# infra_stlink.net
KiCad netlist of a schematic drawn in Altium Designer
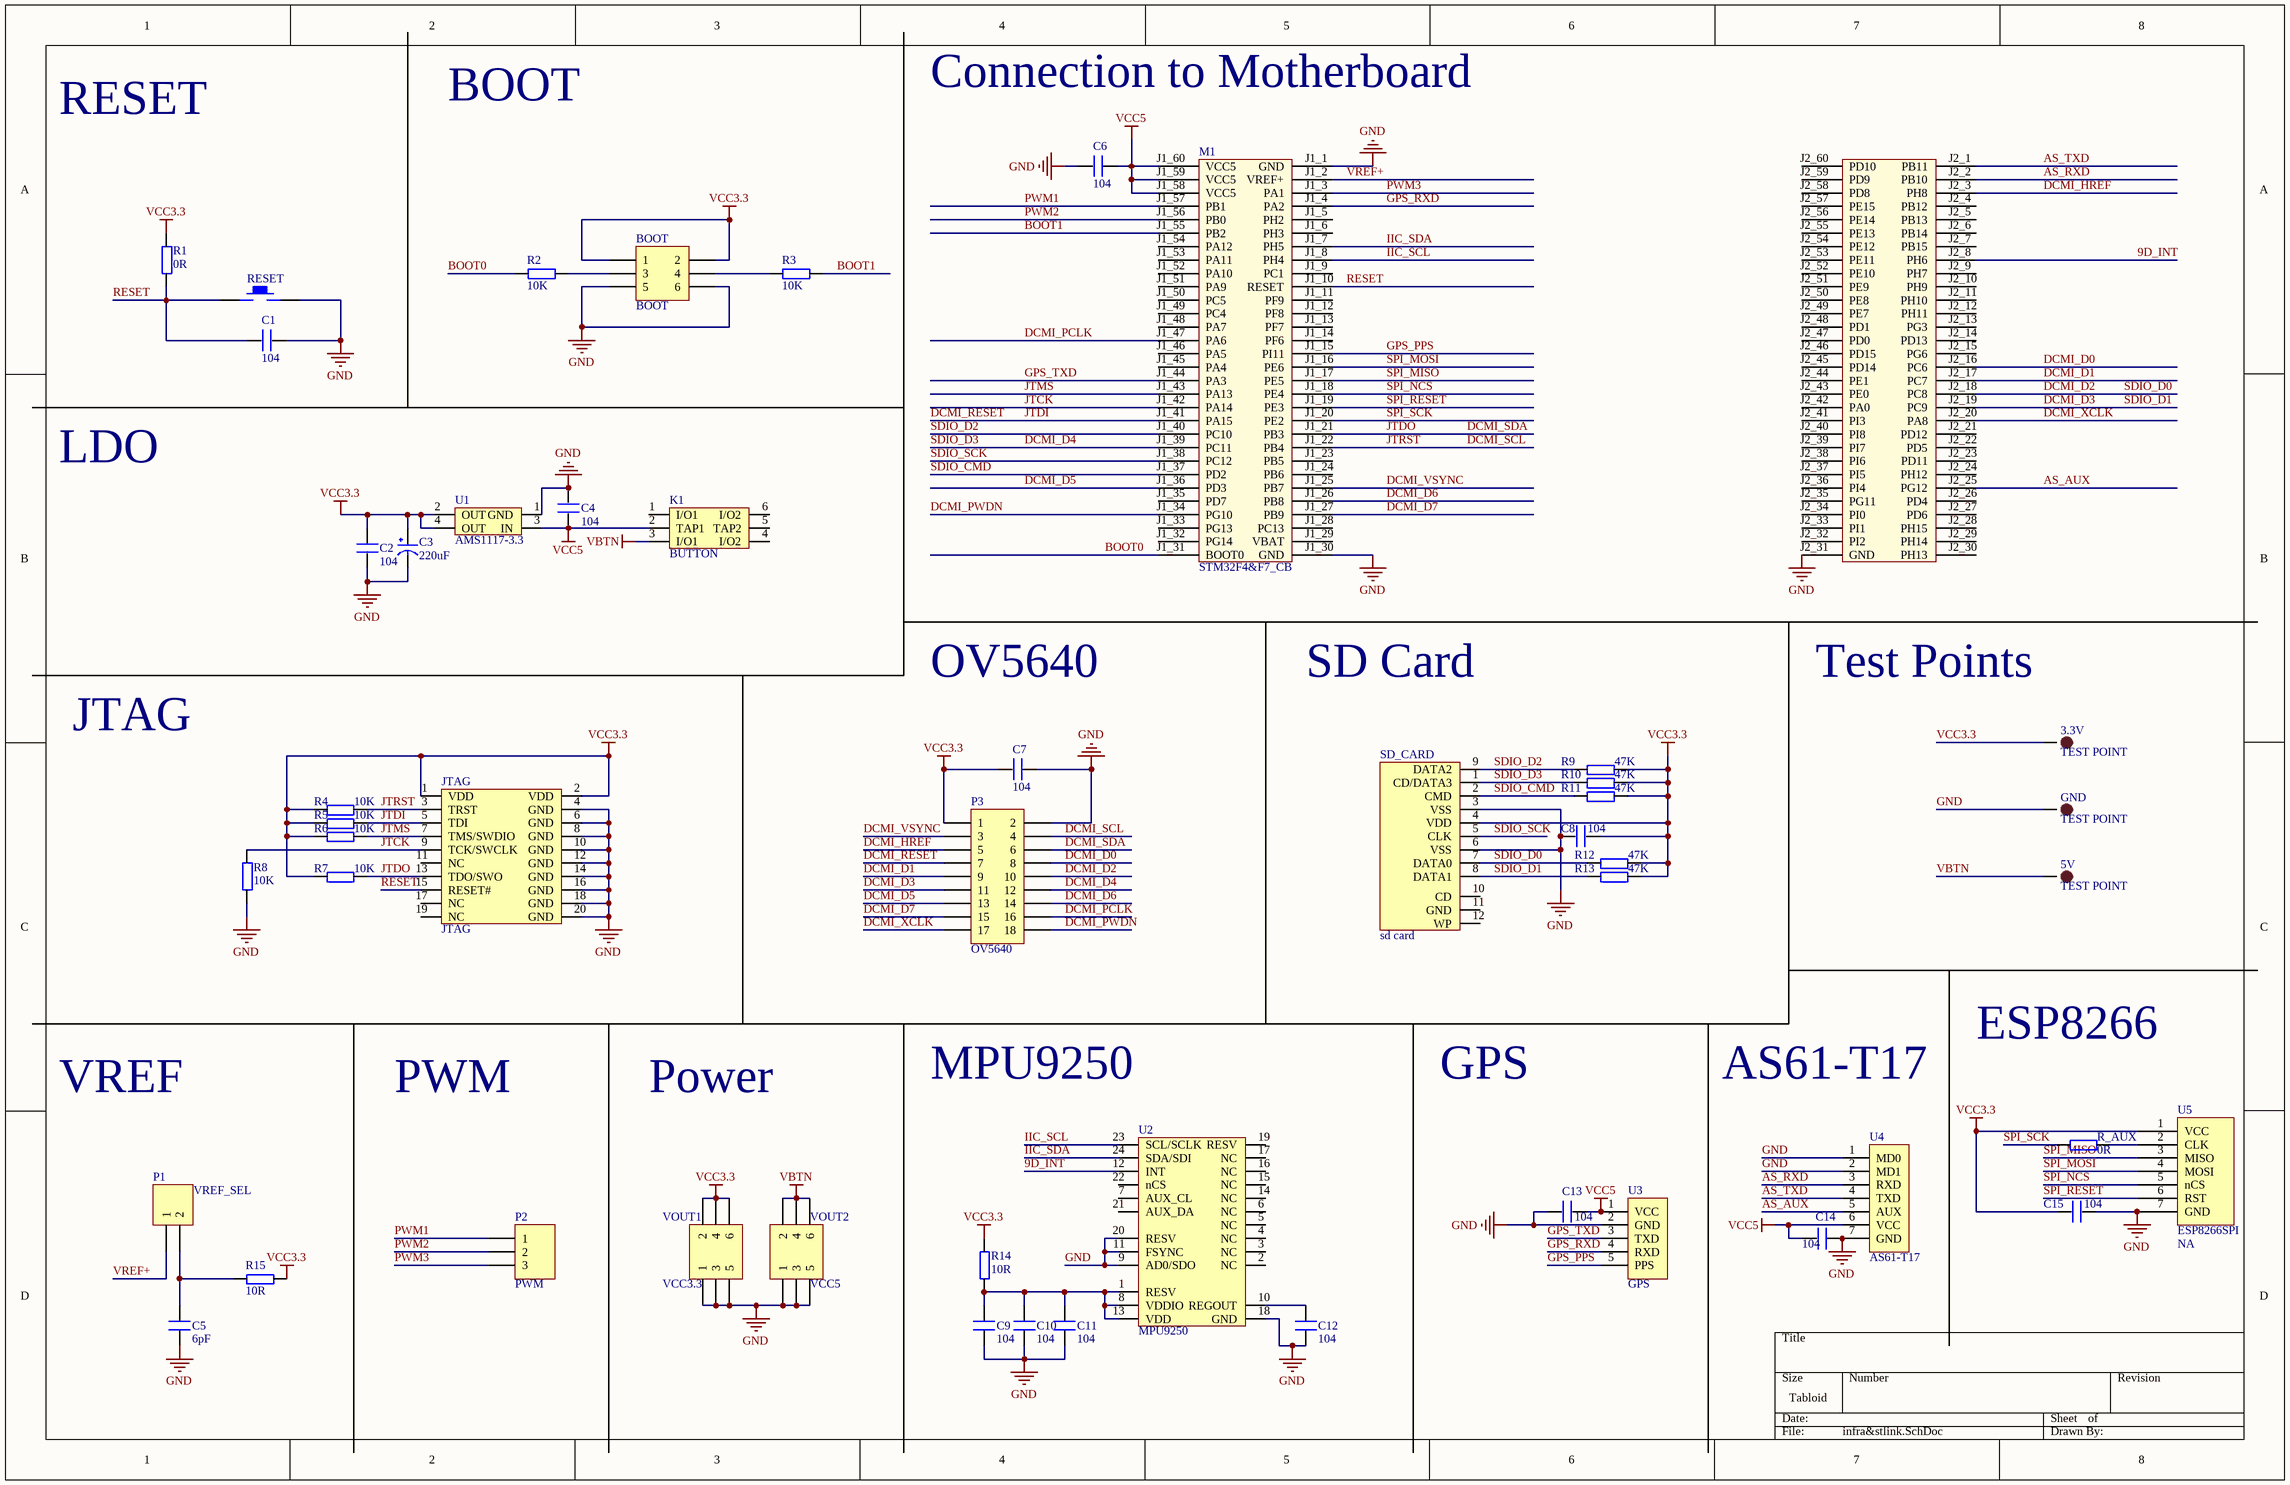
[diagram p0: infra&stlink.SchDoc]

(export (version "E")
  (design (tool "Eeschema 10.0.6"))
  (components
    (comp (ref "3.3V")
      (value "TEST POINT")
      (footprint "TP-1.5")
      (description "测试点")
      (libsource (lib "STM32F767核心板封装库") (part "TEST-POINT"))
    )
    (comp (ref "5V")
      (value "TEST POINT")
      (footprint "TP-1.5")
      (description "测试点")
      (libsource (lib "STM32F767核心板封装库") (part "TEST-POINT"))
    )
    (comp (ref "BOOT")
      (value "BOOT")
      (footprint "HDR2X3")
      (description "Header, 3-Pin, Dual row")
      (fields (field (name "PUBLISHER") "Altium Limited"))
      (libsource (lib "阿波罗STM32F4&F7底板封装库") (part "Header 3X2"))
    )
    (comp (ref "C1") (value "104") (footprint "0805") (libsource (lib "阿波罗STM32F4&F7底板封装库") (part "C")))
    (comp (ref "C2") (value "104") (footprint "0805") (libsource (lib "阿波罗STM32F4&F7底板封装库") (part "C")))
    (comp (ref "C3")
      (value "220uF")
      (footprint "CC6.56.5")
      (libsource (lib "阿波罗STM32F4&F7底板封装库") (part "CAP"))
    )
    (comp (ref "C4") (value "104") (footprint "0805") (libsource (lib "阿波罗STM32F4&F7底板封装库") (part "C")))
    (comp (ref "C5") (value "6pF") (footprint "0805") (libsource (lib "STM32F767核心板封装库") (part "C")))
    (comp (ref "C6") (value "104") (footprint "0805") (libsource (lib "阿波罗STM32F4&F7底板封装库") (part "C")))
    (comp (ref "C7") (value "104") (footprint "0805") (libsource (lib "STM32F767核心板封装库") (part "C")))
    (comp (ref "C8") (value "104") (footprint "0805") (libsource (lib "阿波罗STM32F4&F7底板封装库") (part "C")))
    (comp (ref "C9") (value "104") (footprint "0805") (libsource (lib "阿波罗STM32F4&F7底板封装库") (part "C")))
    (comp (ref "C10") (value "104") (footprint "0805") (libsource (lib "阿波罗STM32F4&F7底板封装库") (part "C")))
    (comp (ref "C11") (value "104") (footprint "0805") (libsource (lib "阿波罗STM32F4&F7底板封装库") (part "C")))
    (comp (ref "C12") (value "104") (footprint "0805") (libsource (lib "阿波罗STM32F4&F7底板封装库") (part "C")))
    (comp (ref "C13") (value "104") (footprint "0805") (libsource (lib "阿波罗STM32F4&F7底板封装库") (part "C")))
    (comp (ref "C14") (value "104") (footprint "0805") (libsource (lib "阿波罗STM32F4&F7底板封装库") (part "C")))
    (comp (ref "C15") (value "104") (footprint "0805") (libsource (lib "阿波罗STM32F4&F7底板封装库") (part "C")))
    (comp (ref "GND")
      (value "TEST POINT")
      (footprint "TP-1.5")
      (description "测试点")
      (libsource (lib "STM32F767核心板封装库") (part "TEST-POINT"))
    )
    (comp (ref "JTAG")
      (value "JTAG")
      (footprint "JTAG_20")
      (libsource (lib "阿波罗STM32F4&F7底板封装库") (part "JTAG"))
    )
    (comp (ref "K1")
      (value "BUTTON")
      (footprint "BTN8.5*8.5")
      (libsource (lib "阿波罗STM32F4&F7底板封装库") (part "BUTTON"))
    )
    (comp (ref "M1")
      (value "STM32F4&F7_CB")
      (footprint "STM32F4&F7_CB")
      (description "F429/746 Core Board")
      (libsource (lib "阿波罗STM32F4&F7底板封装库") (part "STM32F4&F7_CB"))
    )
    (comp (ref "P1")
      (value "VREF_SEL")
      (footprint "HDR1X2")
      (description "Header, 2-Pin")
      (fields (field (name "PUBLISHER") "Altium Limited"))
      (libsource (lib "阿波罗STM32F4&F7底板封装库") (part "Header 2"))
    )
    (comp (ref "P2")
      (value "PWM")
      (footprint "HDR1X3")
      (description "Header, 3-Pin")
      (fields (field (name "PUBLISHER") "Altium Limited"))
      (libsource (lib "Miscellaneous Connectors") (part "Header 3"))
    )
    (comp (ref "P3")
      (value "OV5640")
      (footprint "HDR2X9")
      (description "Header, 9-Pin, Dual row")
      (fields (field (name "PUBLISHER") "Altium Limited"))
      (libsource (lib "阿波罗STM32F4&F7底板封装库") (part "Header 9X2"))
    )
    (comp (ref "R1") (value "0R") (footprint "0805") (libsource (lib "STM32F767核心板封装库") (part "R")))
    (comp (ref "R2") (value "10K") (footprint "0805") (libsource (lib "STM32F767核心板封装库") (part "R")))
    (comp (ref "R3") (value "10K") (footprint "0805") (libsource (lib "STM32F767核心板封装库") (part "R")))
    (comp (ref "R4") (value "10K") (footprint "0805") (libsource (lib "STM32F767核心板封装库") (part "R")))
    (comp (ref "R5") (value "10K") (footprint "0805") (libsource (lib "STM32F767核心板封装库") (part "R")))
    (comp (ref "R6") (value "10K") (footprint "0805") (libsource (lib "STM32F767核心板封装库") (part "R")))
    (comp (ref "R7") (value "10K") (footprint "0805") (libsource (lib "STM32F767核心板封装库") (part "R")))
    (comp (ref "R8") (value "10K") (footprint "0805") (libsource (lib "STM32F767核心板封装库") (part "R")))
    (comp (ref "R9") (value "47K") (footprint "0805") (libsource (lib "STM32F767核心板封装库") (part "R")))
    (comp (ref "R10") (value "47K") (footprint "0805") (libsource (lib "STM32F767核心板封装库") (part "R")))
    (comp (ref "R11") (value "47K") (footprint "0805") (libsource (lib "STM32F767核心板封装库") (part "R")))
    (comp (ref "R12") (value "47K") (footprint "0805") (libsource (lib "STM32F767核心板封装库") (part "R")))
    (comp (ref "R13") (value "47K") (footprint "0805") (libsource (lib "STM32F767核心板封装库") (part "R")))
    (comp (ref "R14") (value "10R") (footprint "0805") (libsource (lib "STM32F767核心板封装库") (part "R")))
    (comp (ref "R15") (value "10R") (footprint "0805") (libsource (lib "STM32F767核心板封装库") (part "R")))
    (comp (ref "RESET")
      (value "KEY_M")
      (footprint "KEY_M")
      (libsource (lib "阿波罗STM32F4&F7底板封装库") (part "KEY_M"))
    )
    (comp (ref "R_AUX") (value "0R") (footprint "0805") (libsource (lib "STM32F767核心板封装库") (part "R")))
    (comp (ref "SD_CARD")
      (value "sd card")
      (footprint "SDCARD_L")
      (libsource (lib "阿波罗STM32F4&F7底板封装库") (part "sd card"))
    )
    (comp (ref "U1")
      (value "AMS1117-3.3")
      (footprint "AMS1117")
      (libsource (lib "阿波罗STM32F4&F7底板封装库") (part "AMS1117"))
    )
    (comp (ref "U2")
      (value "MPU9250")
      (footprint "QFN24-t")
      (description "9轴运动处理传感器")
      (libsource (lib "阿波罗STM32F4&F7底板封装库") (part "MPU9250"))
    )
    (comp (ref "U3")
      (value "GPS")
      (footprint "HDR1X5")
      (description "Header, 5-Pin")
      (fields (field (name "PUBLISHER") "Altium Limited"))
      (libsource (lib "Miscellaneous Connectors") (part "Header 5"))
    )
    (comp (ref "U4")
      (value "AS61-T17")
      (footprint "HDR1X7")
      (description "Header, 7-Pin")
      (fields (field (name "PUBLISHER") "Altium Limited"))
      (libsource (lib "Miscellaneous Connectors") (part "Header 7"))
    )
    (comp (ref "U5")
      (value "NA")
      (footprint "Edge Connector7")
      (libsource (lib "esp8266spi") (part "ESP8266SPI"))
    )
    (comp (ref "VOUT1")
      (value "VCC3.3")
      (footprint "HDR2X3")
      (description "Header, 3-Pin, Dual row")
      (fields (field (name "PUBLISHER") "Altium Limited"))
      (libsource (lib "Miscellaneous Connectors") (part "Header 3X2"))
    )
    (comp (ref "VOUT2")
      (value "VCC5")
      (footprint "HDR2X3")
      (description "Header, 3-Pin, Dual row")
      (fields (field (name "PUBLISHER") "Altium Limited"))
      (libsource (lib "Miscellaneous Connectors") (part "Header 3X2"))
    )
  )
  (nets
    (net (code "1") (name "/9D_INT") (class "Default")
      (node (ref "M1") (pin "J2_8") (pinfunction "PH6_J2_8") (pintype "passive"))
      (node (ref "U2") (pin "12") (pinfunction "INT_12") (pintype "passive"))
    )
    (net (code "2") (name "/AS_AUX") (class "Default")
      (node (ref "M1") (pin "J2_25") (pinfunction "PG12_J2_25") (pintype "passive"))
      (node (ref "U4") (pin "5") (pinfunction "AUX_5") (pintype "passive"))
    )
    (net (code "3") (name "/AS_RXD") (class "Default")
      (node (ref "M1") (pin "J2_2") (pinfunction "PB10_J2_2") (pintype "passive"))
      (node (ref "U4") (pin "3") (pinfunction "RXD_3") (pintype "passive"))
    )
    (net (code "4") (name "/AS_TXD") (class "Default")
      (node (ref "M1") (pin "J2_1") (pinfunction "PB11_J2_1") (pintype "passive"))
      (node (ref "U4") (pin "4") (pinfunction "TXD_4") (pintype "passive"))
    )
    (net (code "5") (name "/BOOT0") (class "Default")
      (node (ref "M1") (pin "J1_31") (pinfunction "BOOT0_J1_31") (pintype "passive"))
      (node (ref "R2") (pin "1") (pintype "passive"))
    )
    (net (code "6") (name "/BOOT1") (class "Default")
      (node (ref "M1") (pin "J1_55") (pinfunction "PB2_J1_55") (pintype "passive"))
      (node (ref "R3") (pin "2") (pintype "passive"))
    )
    (net (code "7") (name "/DCMI_D0") (class "Default")
      (node (ref "M1") (pin "J2_16") (pinfunction "PC6_J2_16") (pintype "passive"))
      (node (ref "P3") (pin "8") (pinfunction "8_8") (pintype "passive"))
    )
    (net (code "8") (name "/DCMI_D1") (class "Default")
      (node (ref "M1") (pin "J2_17") (pinfunction "PC7_J2_17") (pintype "passive"))
      (node (ref "P3") (pin "9") (pinfunction "9_9") (pintype "passive"))
    )
    (net (code "9") (name "/DCMI_D2") (class "Default")
      (node (ref "M1") (pin "J2_18") (pinfunction "PC8_J2_18") (pintype "passive"))
      (node (ref "P3") (pin "10") (pinfunction "10_10") (pintype "passive"))
      (node (ref "R12") (pin "1") (pintype "passive"))
      (node (ref "SD_CARD") (pin "7") (pinfunction "DATA0_7") (pintype "passive"))
    )
    (net (code "10") (name "/DCMI_D3") (class "Default")
      (node (ref "M1") (pin "J2_19") (pinfunction "PC9_J2_19") (pintype "passive"))
      (node (ref "P3") (pin "11") (pinfunction "11_11") (pintype "passive"))
      (node (ref "R13") (pin "1") (pintype "passive"))
      (node (ref "SD_CARD") (pin "8") (pinfunction "DATA1_8") (pintype "passive"))
    )
    (net (code "11") (name "/DCMI_D4") (class "Default")
      (node (ref "M1") (pin "J1_39") (pinfunction "PC11_J1_39") (pintype "passive"))
      (node (ref "P3") (pin "12") (pinfunction "12_12") (pintype "passive"))
      (node (ref "R10") (pin "1") (pintype "passive"))
      (node (ref "SD_CARD") (pin "1") (pinfunction "CD/DATA3_1") (pintype "passive"))
    )
    (net (code "12") (name "/DCMI_D5") (class "Default")
      (node (ref "M1") (pin "J1_36") (pinfunction "PD3_J1_36") (pintype "passive"))
      (node (ref "P3") (pin "13") (pinfunction "13_13") (pintype "passive"))
    )
    (net (code "13") (name "/DCMI_D6") (class "Default")
      (node (ref "M1") (pin "J1_26") (pinfunction "PB8_J1_26") (pintype "passive"))
      (node (ref "P3") (pin "14") (pinfunction "14_14") (pintype "passive"))
    )
    (net (code "14") (name "/DCMI_D7") (class "Default")
      (node (ref "M1") (pin "J1_27") (pinfunction "PB9_J1_27") (pintype "passive"))
      (node (ref "P3") (pin "15") (pinfunction "15_15") (pintype "passive"))
    )
    (net (code "15") (name "/DCMI_HREF") (class "Default")
      (node (ref "M1") (pin "J2_3") (pinfunction "PH8_J2_3") (pintype "passive"))
      (node (ref "P3") (pin "5") (pinfunction "5_5") (pintype "passive"))
    )
    (net (code "16") (name "/DCMI_PCLK") (class "Default")
      (node (ref "M1") (pin "J1_47") (pinfunction "PA6_J1_47") (pintype "passive"))
      (node (ref "P3") (pin "16") (pinfunction "16_16") (pintype "passive"))
    )
    (net (code "17") (name "/DCMI_PWDN") (class "Default")
      (node (ref "M1") (pin "J1_34") (pinfunction "PG10_J1_34") (pintype "passive"))
      (node (ref "P3") (pin "18") (pinfunction "18_18") (pintype "passive"))
    )
    (net (code "18") (name "/DCMI_RESET") (class "Default")
      (node (ref "JTAG") (pin "5") (pinfunction "TDI_5") (pintype "passive"))
      (node (ref "M1") (pin "J1_41") (pinfunction "PA15_J1_41") (pintype "passive"))
      (node (ref "P3") (pin "7") (pinfunction "7_7") (pintype "passive"))
      (node (ref "R5") (pin "2") (pintype "passive"))
    )
    (net (code "19") (name "/DCMI_SCL") (class "Default")
      (node (ref "JTAG") (pin "3") (pinfunction "TRST_3") (pintype "passive"))
      (node (ref "M1") (pin "J1_22") (pinfunction "PB4_J1_22") (pintype "passive"))
      (node (ref "P3") (pin "4") (pinfunction "4_4") (pintype "passive"))
      (node (ref "R4") (pin "2") (pintype "passive"))
    )
    (net (code "20") (name "/DCMI_SDA") (class "Default")
      (node (ref "JTAG") (pin "13") (pinfunction "TDO/SWO_13") (pintype "passive"))
      (node (ref "M1") (pin "J1_21") (pinfunction "PB3_J1_21") (pintype "passive"))
      (node (ref "P3") (pin "6") (pinfunction "6_6") (pintype "passive"))
      (node (ref "R7") (pin "2") (pintype "passive"))
    )
    (net (code "21") (name "/DCMI_VSYNC") (class "Default")
      (node (ref "M1") (pin "J1_25") (pinfunction "PB7_J1_25") (pintype "passive"))
      (node (ref "P3") (pin "3") (pinfunction "3_3") (pintype "passive"))
    )
    (net (code "22") (name "/DCMI_XCLK") (class "Default")
      (node (ref "M1") (pin "J2_20") (pinfunction "PA8_J2_20") (pintype "passive"))
      (node (ref "P3") (pin "17") (pinfunction "17_17") (pintype "passive"))
    )
    (net (code "23") (name "/GPS_PPS") (class "Default")
      (node (ref "M1") (pin "J1_15") (pinfunction "PI11_J1_15") (pintype "passive"))
      (node (ref "U3") (pin "5") (pinfunction "PPS_5") (pintype "passive"))
    )
    (net (code "24") (name "/GPS_RXD") (class "Default")
      (node (ref "M1") (pin "J1_4") (pinfunction "PA2_J1_4") (pintype "passive"))
      (node (ref "U3") (pin "4") (pinfunction "RXD_4") (pintype "passive"))
    )
    (net (code "25") (name "/GPS_TXD") (class "Default")
      (node (ref "M1") (pin "J1_44") (pinfunction "PA3_J1_44") (pintype "passive"))
      (node (ref "U3") (pin "3") (pinfunction "TXD_3") (pintype "passive"))
    )
    (net (code "26") (name "/IIC_SCL") (class "Default")
      (node (ref "M1") (pin "J1_8") (pinfunction "PH4_J1_8") (pintype "passive"))
      (node (ref "U2") (pin "23") (pinfunction "SCL/SCLK_23") (pintype "passive"))
    )
    (net (code "27") (name "/IIC_SDA") (class "Default")
      (node (ref "M1") (pin "J1_7") (pinfunction "PH5_J1_7") (pintype "passive"))
      (node (ref "U2") (pin "24") (pinfunction "SDA/SDI_24") (pintype "passive"))
    )
    (net (code "28") (name "/JTCK") (class "Default")
      (node (ref "JTAG") (pin "9") (pinfunction "TCK/SWCLK_9") (pintype "passive"))
      (node (ref "M1") (pin "J1_42") (pinfunction "PA14_J1_42") (pintype "passive"))
      (node (ref "R8") (pin "2") (pintype "passive"))
    )
    (net (code "29") (name "/JTMS") (class "Default")
      (node (ref "JTAG") (pin "7") (pinfunction "TMS/SWDIO_7") (pintype "passive"))
      (node (ref "M1") (pin "J1_43") (pinfunction "PA13_J1_43") (pintype "passive"))
      (node (ref "R6") (pin "2") (pintype "passive"))
    )
    (net (code "30") (name "/PWM1") (class "Default")
      (node (ref "M1") (pin "J1_57") (pinfunction "PB1_J1_57") (pintype "passive"))
      (node (ref "P2") (pin "1") (pinfunction "1_1") (pintype "passive"))
    )
    (net (code "31") (name "/PWM2") (class "Default")
      (node (ref "M1") (pin "J1_56") (pinfunction "PB0_J1_56") (pintype "passive"))
      (node (ref "P2") (pin "2") (pinfunction "2_2") (pintype "passive"))
    )
    (net (code "32") (name "/PWM3") (class "Default")
      (node (ref "M1") (pin "J1_3") (pinfunction "PA1_J1_3") (pintype "passive"))
      (node (ref "P2") (pin "3") (pinfunction "3_3") (pintype "passive"))
    )
    (net (code "33") (name "/RESET") (class "Default")
      (node (ref "C1") (pin "1") (pintype "passive"))
      (node (ref "JTAG") (pin "15") (pinfunction "RESET#_15") (pintype "passive"))
      (node (ref "M1") (pin "J1_10") (pinfunction "RESET_J1_10") (pintype "passive"))
      (node (ref "R1") (pin "1") (pintype "passive"))
      (node (ref "RESET") (pin "1") (pinfunction "1_1") (pintype "passive"))
    )
    (net (code "34") (name "/SDIO_CMD") (class "Default")
      (node (ref "M1") (pin "J1_37") (pinfunction "PD2_J1_37") (pintype "passive"))
      (node (ref "R11") (pin "1") (pintype "passive"))
      (node (ref "SD_CARD") (pin "2") (pinfunction "CMD_2") (pintype "passive"))
    )
    (net (code "35") (name "/SDIO_D2") (class "Default")
      (node (ref "M1") (pin "J1_40") (pinfunction "PC10_J1_40") (pintype "passive"))
      (node (ref "R9") (pin "1") (pintype "passive"))
      (node (ref "SD_CARD") (pin "9") (pinfunction "DATA2_9") (pintype "passive"))
    )
    (net (code "36") (name "/SDIO_SCK") (class "Default")
      (node (ref "M1") (pin "J1_38") (pinfunction "PC12_J1_38") (pintype "passive"))
      (node (ref "SD_CARD") (pin "5") (pinfunction "CLK_5") (pintype "passive"))
    )
    (net (code "37") (name "/SPI_MISO") (class "Default")
      (node (ref "M1") (pin "J1_17") (pinfunction "PE5_J1_17") (pintype "passive"))
      (node (ref "U5") (pin "3") (pinfunction "MISO_3") (pintype "passive"))
    )
    (net (code "38") (name "/SPI_MOSI") (class "Default")
      (node (ref "M1") (pin "J1_16") (pinfunction "PE6_J1_16") (pintype "passive"))
      (node (ref "U5") (pin "4") (pinfunction "MOSI_4") (pintype "passive"))
    )
    (net (code "39") (name "/SPI_NCS") (class "Default")
      (node (ref "M1") (pin "J1_18") (pinfunction "PE4_J1_18") (pintype "passive"))
      (node (ref "U5") (pin "5") (pinfunction "nCS_5") (pintype "passive"))
    )
    (net (code "40") (name "/SPI_RESET") (class "Default")
      (node (ref "M1") (pin "J1_19") (pinfunction "PE3_J1_19") (pintype "passive"))
      (node (ref "U5") (pin "6") (pinfunction "RST_6") (pintype "passive"))
    )
    (net (code "41") (name "/SPI_SCK") (class "Default")
      (node (ref "M1") (pin "J1_20") (pinfunction "PE2_J1_20") (pintype "passive"))
      (node (ref "R_AUX") (pin "1") (pintype "passive"))
    )
    (net (code "42") (name "/VREF+") (class "Default")
      (node (ref "M1") (pin "J1_2") (pinfunction "VREF+_J1_2") (pintype "passive"))
      (node (ref "P1") (pin "1") (pinfunction "1_1") (pintype "passive"))
    )
    (net (code "43") (name "GND") (class "Default")
      (node (ref "BOOT") (pin "5") (pinfunction "5_5") (pintype "passive"))
      (node (ref "BOOT") (pin "6") (pinfunction "6_6") (pintype "passive"))
      (node (ref "C1") (pin "2") (pintype "passive"))
      (node (ref "C10") (pin "1") (pintype "passive"))
      (node (ref "C11") (pin "1") (pintype "passive"))
      (node (ref "C12") (pin "1") (pintype "passive"))
      (node (ref "C13") (pin "1") (pintype "passive"))
      (node (ref "C14") (pin "1") (pintype "passive"))
      (node (ref "C15") (pin "2") (pintype "passive"))
      (node (ref "C2") (pin "1") (pintype "passive"))
      (node (ref "C3") (pin "2") (pinfunction "GND_2") (pintype "passive"))
      (node (ref "C4") (pin "2") (pintype "passive"))
      (node (ref "C5") (pin "1") (pintype "passive"))
      (node (ref "C6") (pin "1") (pintype "passive"))
      (node (ref "C7") (pin "2") (pintype "passive"))
      (node (ref "C8") (pin "1") (pintype "passive"))
      (node (ref "C9") (pin "1") (pintype "passive"))
      (node (ref "GND") (pin "1") (pinfunction "1_1") (pintype "passive"))
      (node (ref "JTAG") (pin "10") (pinfunction "GND_10") (pintype "passive"))
      (node (ref "JTAG") (pin "12") (pinfunction "GND_12") (pintype "passive"))
      (node (ref "JTAG") (pin "14") (pinfunction "GND_14") (pintype "passive"))
      (node (ref "JTAG") (pin "16") (pinfunction "GND_16") (pintype "passive"))
      (node (ref "JTAG") (pin "18") (pinfunction "GND_18") (pintype "passive"))
      (node (ref "JTAG") (pin "20") (pinfunction "GND_20") (pintype "passive"))
      (node (ref "JTAG") (pin "4") (pinfunction "GND_4") (pintype "passive"))
      (node (ref "JTAG") (pin "6") (pinfunction "GND_6") (pintype "passive"))
      (node (ref "JTAG") (pin "8") (pinfunction "GND_8") (pintype "passive"))
      (node (ref "M1") (pin "J1_1") (pinfunction "GND_J1_1") (pintype "passive"))
      (node (ref "M1") (pin "J1_30") (pinfunction "GND_J1_30") (pintype "passive"))
      (node (ref "M1") (pin "J2_31") (pinfunction "GND_J2_31") (pintype "passive"))
      (node (ref "P3") (pin "2") (pinfunction "2_2") (pintype "passive"))
      (node (ref "R8") (pin "1") (pintype "passive"))
      (node (ref "RESET") (pin "2") (pinfunction "2_2") (pintype "passive"))
      (node (ref "SD_CARD") (pin "3") (pinfunction "VSS_3") (pintype "passive"))
      (node (ref "SD_CARD") (pin "6") (pinfunction "VSS_6") (pintype "passive"))
      (node (ref "U1") (pin "1") (pinfunction "GND_1") (pintype "passive"))
      (node (ref "U2") (pin "11") (pinfunction "FSYNC_11") (pintype "passive"))
      (node (ref "U2") (pin "18") (pinfunction "GND_18") (pintype "passive"))
      (node (ref "U2") (pin "20") (pinfunction "RESV_20") (pintype "passive"))
      (node (ref "U2") (pin "9") (pinfunction "AD0/SDO_9") (pintype "passive"))
      (node (ref "U3") (pin "2") (pinfunction "GND_2") (pintype "passive"))
      (node (ref "U4") (pin "1") (pinfunction "MD0_1") (pintype "passive"))
      (node (ref "U4") (pin "2") (pinfunction "MD1_2") (pintype "passive"))
      (node (ref "U4") (pin "7") (pinfunction "GND_7") (pintype "passive"))
      (node (ref "U5") (pin "7") (pinfunction "GND_7") (pintype "passive"))
      (node (ref "VOUT1") (pin "1") (pinfunction "1_1") (pintype "passive"))
      (node (ref "VOUT1") (pin "3") (pinfunction "3_3") (pintype "passive"))
      (node (ref "VOUT1") (pin "5") (pinfunction "5_5") (pintype "passive"))
      (node (ref "VOUT2") (pin "1") (pinfunction "1_1") (pintype "passive"))
      (node (ref "VOUT2") (pin "3") (pinfunction "3_3") (pintype "passive"))
      (node (ref "VOUT2") (pin "5") (pinfunction "5_5") (pintype "passive"))
    )
    (net (code "44") (name "Net-(BOOT-Pad3)") (class "Default")
      (node (ref "BOOT") (pin "3") (pinfunction "3_3") (pintype "passive"))
      (node (ref "R2") (pin "2") (pintype "passive"))
    )
    (net (code "45") (name "Net-(BOOT-Pad4)") (class "Default")
      (node (ref "BOOT") (pin "4") (pinfunction "4_4") (pintype "passive"))
      (node (ref "R3") (pin "1") (pintype "passive"))
    )
    (net (code "46") (name "Net-(C5-Pad2)") (class "Default")
      (node (ref "C5") (pin "2") (pintype "passive"))
      (node (ref "P1") (pin "2") (pinfunction "2_2") (pintype "passive"))
      (node (ref "R15") (pin "1") (pintype "passive"))
    )
    (net (code "47") (name "Net-(U2-REGOUT)") (class "Default")
      (node (ref "C12") (pin "2") (pintype "passive"))
      (node (ref "U2") (pin "10") (pinfunction "REGOUT_10") (pintype "passive"))
    )
    (net (code "48") (name "Net-(U2-VDD)") (class "Default")
      (node (ref "C10") (pin "2") (pintype "passive"))
      (node (ref "C11") (pin "2") (pintype "passive"))
      (node (ref "C9") (pin "2") (pintype "passive"))
      (node (ref "R14") (pin "1") (pintype "passive"))
      (node (ref "U2") (pin "1") (pinfunction "RESV_1") (pintype "passive"))
      (node (ref "U2") (pin "13") (pinfunction "VDD_13") (pintype "passive"))
      (node (ref "U2") (pin "8") (pinfunction "VDDIO_8") (pintype "passive"))
    )
    (net (code "49") (name "Net-(U5-CLK)") (class "Default")
      (node (ref "R_AUX") (pin "2") (pintype "passive"))
      (node (ref "U5") (pin "2") (pinfunction "CLK_2") (pintype "passive"))
    )
    (net (code "50") (name "VBTN") (class "Default")
      (node (ref "5V") (pin "1") (pinfunction "1_1") (pintype "passive"))
      (node (ref "K1") (pin "3") (pinfunction "I/O1_3") (pintype "passive"))
      (node (ref "VOUT2") (pin "2") (pinfunction "2_2") (pintype "passive"))
      (node (ref "VOUT2") (pin "4") (pinfunction "4_4") (pintype "passive"))
      (node (ref "VOUT2") (pin "6") (pinfunction "6_6") (pintype "passive"))
    )
    (net (code "51") (name "VCC3.3") (class "Default")
      (node (ref "3.3V") (pin "1") (pinfunction "1_1") (pintype "passive"))
      (node (ref "BOOT") (pin "1") (pinfunction "1_1") (pintype "passive"))
      (node (ref "BOOT") (pin "2") (pinfunction "2_2") (pintype "passive"))
      (node (ref "C15") (pin "1") (pintype "passive"))
      (node (ref "C2") (pin "2") (pintype "passive"))
      (node (ref "C3") (pin "1") (pinfunction "VCC_1") (pintype "passive"))
      (node (ref "C7") (pin "1") (pintype "passive"))
      (node (ref "C8") (pin "2") (pintype "passive"))
      (node (ref "JTAG") (pin "1") (pinfunction "VDD_1") (pintype "passive"))
      (node (ref "JTAG") (pin "2") (pinfunction "VDD_2") (pintype "passive"))
      (node (ref "P3") (pin "1") (pinfunction "1_1") (pintype "passive"))
      (node (ref "R1") (pin "2") (pintype "passive"))
      (node (ref "R10") (pin "2") (pintype "passive"))
      (node (ref "R11") (pin "2") (pintype "passive"))
      (node (ref "R12") (pin "2") (pintype "passive"))
      (node (ref "R13") (pin "2") (pintype "passive"))
      (node (ref "R14") (pin "2") (pintype "passive"))
      (node (ref "R15") (pin "2") (pintype "passive"))
      (node (ref "R4") (pin "1") (pintype "passive"))
      (node (ref "R5") (pin "1") (pintype "passive"))
      (node (ref "R6") (pin "1") (pintype "passive"))
      (node (ref "R7") (pin "1") (pintype "passive"))
      (node (ref "R9") (pin "2") (pintype "passive"))
      (node (ref "SD_CARD") (pin "4") (pinfunction "VDD_4") (pintype "passive"))
      (node (ref "U1") (pin "2") (pinfunction "OUT_2") (pintype "passive"))
      (node (ref "U1") (pin "4") (pinfunction "OUT_4") (pintype "passive"))
      (node (ref "U5") (pin "1") (pinfunction "VCC_1") (pintype "passive"))
      (node (ref "VOUT1") (pin "2") (pinfunction "2_2") (pintype "passive"))
      (node (ref "VOUT1") (pin "4") (pinfunction "4_4") (pintype "passive"))
      (node (ref "VOUT1") (pin "6") (pinfunction "6_6") (pintype "passive"))
    )
    (net (code "52") (name "VCC5") (class "Default")
      (node (ref "C13") (pin "2") (pintype "passive"))
      (node (ref "C14") (pin "2") (pintype "passive"))
      (node (ref "C4") (pin "1") (pintype "passive"))
      (node (ref "C6") (pin "2") (pintype "passive"))
      (node (ref "K1") (pin "2") (pinfunction "TAP1_2") (pintype "passive"))
      (node (ref "M1") (pin "J1_58") (pinfunction "VCC5_J1_58") (pintype "passive"))
      (node (ref "M1") (pin "J1_59") (pinfunction "VCC5_J1_59") (pintype "passive"))
      (node (ref "M1") (pin "J1_60") (pinfunction "VCC5_J1_60") (pintype "passive"))
      (node (ref "U1") (pin "3") (pinfunction "IN_3") (pintype "passive"))
      (node (ref "U3") (pin "1") (pinfunction "VCC_1") (pintype "passive"))
      (node (ref "U4") (pin "6") (pinfunction "VCC_6") (pintype "passive"))
    )
    (net (code "53") (name "unconnected-(JTAG-NC-Pad11)") (class "Default")
      (node (ref "JTAG") (pin "11") (pinfunction "NC_11") (pintype "passive"))
    )
    (net (code "54") (name "unconnected-(JTAG-NC-Pad17)") (class "Default")
      (node (ref "JTAG") (pin "17") (pinfunction "NC_17") (pintype "passive"))
    )
    (net (code "55") (name "unconnected-(JTAG-NC-Pad19)") (class "Default")
      (node (ref "JTAG") (pin "19") (pinfunction "NC_19") (pintype "passive"))
    )
    (net (code "56") (name "unconnected-(K1-I{slash}O1-Pad1)") (class "Default")
      (node (ref "K1") (pin "1") (pinfunction "I/O1_1") (pintype "passive"))
    )
    (net (code "57") (name "unconnected-(K1-I{slash}O2-Pad4)") (class "Default")
      (node (ref "K1") (pin "4") (pinfunction "I/O2_4") (pintype "passive"))
    )
    (net (code "58") (name "unconnected-(K1-I{slash}O2-Pad6)") (class "Default")
      (node (ref "K1") (pin "6") (pinfunction "I/O2_6") (pintype "passive"))
    )
    (net (code "59") (name "unconnected-(K1-TAP2-Pad5)") (class "Default")
      (node (ref "K1") (pin "5") (pinfunction "TAP2_5") (pintype "passive"))
    )
    (net (code "60") (name "unconnected-(M1-PA0-PadJ2_42)") (class "Default")
      (node (ref "M1") (pin "J2_42") (pinfunction "PA0_J2_42") (pintype "passive"))
    )
    (net (code "61") (name "unconnected-(M1-PA4-PadJ1_45)") (class "Default")
      (node (ref "M1") (pin "J1_45") (pinfunction "PA4_J1_45") (pintype "passive"))
    )
    (net (code "62") (name "unconnected-(M1-PA5-PadJ1_46)") (class "Default")
      (node (ref "M1") (pin "J1_46") (pinfunction "PA5_J1_46") (pintype "passive"))
    )
    (net (code "63") (name "unconnected-(M1-PA7-PadJ1_48)") (class "Default")
      (node (ref "M1") (pin "J1_48") (pinfunction "PA7_J1_48") (pintype "passive"))
    )
    (net (code "64") (name "unconnected-(M1-PA9-PadJ1_51)") (class "Default")
      (node (ref "M1") (pin "J1_51") (pinfunction "PA9_J1_51") (pintype "passive"))
    )
    (net (code "65") (name "unconnected-(M1-PA10-PadJ1_52)") (class "Default")
      (node (ref "M1") (pin "J1_52") (pinfunction "PA10_J1_52") (pintype "passive"))
    )
    (net (code "66") (name "unconnected-(M1-PA11-PadJ1_53)") (class "Default")
      (node (ref "M1") (pin "J1_53") (pinfunction "PA11_J1_53") (pintype "passive"))
    )
    (net (code "67") (name "unconnected-(M1-PA12-PadJ1_54)") (class "Default")
      (node (ref "M1") (pin "J1_54") (pinfunction "PA12_J1_54") (pintype "passive"))
    )
    (net (code "68") (name "unconnected-(M1-PB5-PadJ1_23)") (class "Default")
      (node (ref "M1") (pin "J1_23") (pinfunction "PB5_J1_23") (pintype "passive"))
    )
    (net (code "69") (name "unconnected-(M1-PB6-PadJ1_24)") (class "Default")
      (node (ref "M1") (pin "J1_24") (pinfunction "PB6_J1_24") (pintype "passive"))
    )
    (net (code "70") (name "unconnected-(M1-PB12-PadJ2_4)") (class "Default")
      (node (ref "M1") (pin "J2_4") (pinfunction "PB12_J2_4") (pintype "passive"))
    )
    (net (code "71") (name "unconnected-(M1-PB13-PadJ2_5)") (class "Default")
      (node (ref "M1") (pin "J2_5") (pinfunction "PB13_J2_5") (pintype "passive"))
    )
    (net (code "72") (name "unconnected-(M1-PB14-PadJ2_6)") (class "Default")
      (node (ref "M1") (pin "J2_6") (pinfunction "PB14_J2_6") (pintype "passive"))
    )
    (net (code "73") (name "unconnected-(M1-PB15-PadJ2_7)") (class "Default")
      (node (ref "M1") (pin "J2_7") (pinfunction "PB15_J2_7") (pintype "passive"))
    )
    (net (code "74") (name "unconnected-(M1-PC1-PadJ1_9)") (class "Default")
      (node (ref "M1") (pin "J1_9") (pinfunction "PC1_J1_9") (pintype "passive"))
    )
    (net (code "75") (name "unconnected-(M1-PC4-PadJ1_49)") (class "Default")
      (node (ref "M1") (pin "J1_49") (pinfunction "PC4_J1_49") (pintype "passive"))
    )
    (net (code "76") (name "unconnected-(M1-PC5-PadJ1_50)") (class "Default")
      (node (ref "M1") (pin "J1_50") (pinfunction "PC5_J1_50") (pintype "passive"))
    )
    (net (code "77") (name "unconnected-(M1-PC13-PadJ1_28)") (class "Default")
      (node (ref "M1") (pin "J1_28") (pinfunction "PC13_J1_28") (pintype "passive"))
    )
    (net (code "78") (name "unconnected-(M1-PD0-PadJ2_47)") (class "Default")
      (node (ref "M1") (pin "J2_47") (pinfunction "PD0_J2_47") (pintype "passive"))
    )
    (net (code "79") (name "unconnected-(M1-PD1-PadJ2_48)") (class "Default")
      (node (ref "M1") (pin "J2_48") (pinfunction "PD1_J2_48") (pintype "passive"))
    )
    (net (code "80") (name "unconnected-(M1-PD4-PadJ2_26)") (class "Default")
      (node (ref "M1") (pin "J2_26") (pinfunction "PD4_J2_26") (pintype "passive"))
    )
    (net (code "81") (name "unconnected-(M1-PD5-PadJ2_22)") (class "Default")
      (node (ref "M1") (pin "J2_22") (pinfunction "PD5_J2_22") (pintype "passive"))
    )
    (net (code "82") (name "unconnected-(M1-PD6-PadJ2_27)") (class "Default")
      (node (ref "M1") (pin "J2_27") (pinfunction "PD6_J2_27") (pintype "passive"))
    )
    (net (code "83") (name "unconnected-(M1-PD7-PadJ1_35)") (class "Default")
      (node (ref "M1") (pin "J1_35") (pinfunction "PD7_J1_35") (pintype "passive"))
    )
    (net (code "84") (name "unconnected-(M1-PD8-PadJ2_58)") (class "Default")
      (node (ref "M1") (pin "J2_58") (pinfunction "PD8_J2_58") (pintype "passive"))
    )
    (net (code "85") (name "unconnected-(M1-PD9-PadJ2_59)") (class "Default")
      (node (ref "M1") (pin "J2_59") (pinfunction "PD9_J2_59") (pintype "passive"))
    )
    (net (code "86") (name "unconnected-(M1-PD10-PadJ2_60)") (class "Default")
      (node (ref "M1") (pin "J2_60") (pinfunction "PD10_J2_60") (pintype "passive"))
    )
    (net (code "87") (name "unconnected-(M1-PD11-PadJ2_23)") (class "Default")
      (node (ref "M1") (pin "J2_23") (pinfunction "PD11_J2_23") (pintype "passive"))
    )
    (net (code "88") (name "unconnected-(M1-PD12-PadJ2_21)") (class "Default")
      (node (ref "M1") (pin "J2_21") (pinfunction "PD12_J2_21") (pintype "passive"))
    )
    (net (code "89") (name "unconnected-(M1-PD13-PadJ2_14)") (class "Default")
      (node (ref "M1") (pin "J2_14") (pinfunction "PD13_J2_14") (pintype "passive"))
    )
    (net (code "90") (name "unconnected-(M1-PD14-PadJ2_45)") (class "Default")
      (node (ref "M1") (pin "J2_45") (pinfunction "PD14_J2_45") (pintype "passive"))
    )
    (net (code "91") (name "unconnected-(M1-PD15-PadJ2_46)") (class "Default")
      (node (ref "M1") (pin "J2_46") (pinfunction "PD15_J2_46") (pintype "passive"))
    )
    (net (code "92") (name "unconnected-(M1-PE0-PadJ2_43)") (class "Default")
      (node (ref "M1") (pin "J2_43") (pinfunction "PE0_J2_43") (pintype "passive"))
    )
    (net (code "93") (name "unconnected-(M1-PE1-PadJ2_44)") (class "Default")
      (node (ref "M1") (pin "J2_44") (pinfunction "PE1_J2_44") (pintype "passive"))
    )
    (net (code "94") (name "unconnected-(M1-PE7-PadJ2_49)") (class "Default")
      (node (ref "M1") (pin "J2_49") (pinfunction "PE7_J2_49") (pintype "passive"))
    )
    (net (code "95") (name "unconnected-(M1-PE8-PadJ2_50)") (class "Default")
      (node (ref "M1") (pin "J2_50") (pinfunction "PE8_J2_50") (pintype "passive"))
    )
    (net (code "96") (name "unconnected-(M1-PE9-PadJ2_51)") (class "Default")
      (node (ref "M1") (pin "J2_51") (pinfunction "PE9_J2_51") (pintype "passive"))
    )
    (net (code "97") (name "unconnected-(M1-PE10-PadJ2_52)") (class "Default")
      (node (ref "M1") (pin "J2_52") (pinfunction "PE10_J2_52") (pintype "passive"))
    )
    (net (code "98") (name "unconnected-(M1-PE11-PadJ2_53)") (class "Default")
      (node (ref "M1") (pin "J2_53") (pinfunction "PE11_J2_53") (pintype "passive"))
    )
    (net (code "99") (name "unconnected-(M1-PE12-PadJ2_54)") (class "Default")
      (node (ref "M1") (pin "J2_54") (pinfunction "PE12_J2_54") (pintype "passive"))
    )
    (net (code "100") (name "unconnected-(M1-PE13-PadJ2_55)") (class "Default")
      (node (ref "M1") (pin "J2_55") (pinfunction "PE13_J2_55") (pintype "passive"))
    )
    (net (code "101") (name "unconnected-(M1-PE14-PadJ2_56)") (class "Default")
      (node (ref "M1") (pin "J2_56") (pinfunction "PE14_J2_56") (pintype "passive"))
    )
    (net (code "102") (name "unconnected-(M1-PE15-PadJ2_57)") (class "Default")
      (node (ref "M1") (pin "J2_57") (pinfunction "PE15_J2_57") (pintype "passive"))
    )
    (net (code "103") (name "unconnected-(M1-PF6-PadJ1_14)") (class "Default")
      (node (ref "M1") (pin "J1_14") (pinfunction "PF6_J1_14") (pintype "passive"))
    )
    (net (code "104") (name "unconnected-(M1-PF7-PadJ1_13)") (class "Default")
      (node (ref "M1") (pin "J1_13") (pinfunction "PF7_J1_13") (pintype "passive"))
    )
    (net (code "105") (name "unconnected-(M1-PF8-PadJ1_12)") (class "Default")
      (node (ref "M1") (pin "J1_12") (pinfunction "PF8_J1_12") (pintype "passive"))
    )
    (net (code "106") (name "unconnected-(M1-PF9-PadJ1_11)") (class "Default")
      (node (ref "M1") (pin "J1_11") (pinfunction "PF9_J1_11") (pintype "passive"))
    )
    (net (code "107") (name "unconnected-(M1-PG3-PadJ2_13)") (class "Default")
      (node (ref "M1") (pin "J2_13") (pinfunction "PG3_J2_13") (pintype "passive"))
    )
    (net (code "108") (name "unconnected-(M1-PG6-PadJ2_15)") (class "Default")
      (node (ref "M1") (pin "J2_15") (pinfunction "PG6_J2_15") (pintype "passive"))
    )
    (net (code "109") (name "unconnected-(M1-PG11-PadJ2_35)") (class "Default")
      (node (ref "M1") (pin "J2_35") (pinfunction "PG11_J2_35") (pintype "passive"))
    )
    (net (code "110") (name "unconnected-(M1-PG13-PadJ1_33)") (class "Default")
      (node (ref "M1") (pin "J1_33") (pinfunction "PG13_J1_33") (pintype "passive"))
    )
    (net (code "111") (name "unconnected-(M1-PG14-PadJ1_32)") (class "Default")
      (node (ref "M1") (pin "J1_32") (pinfunction "PG14_J1_32") (pintype "passive"))
    )
    (net (code "112") (name "unconnected-(M1-PH2-PadJ1_5)") (class "Default")
      (node (ref "M1") (pin "J1_5") (pinfunction "PH2_J1_5") (pintype "passive"))
    )
    (net (code "113") (name "unconnected-(M1-PH3-PadJ1_6)") (class "Default")
      (node (ref "M1") (pin "J1_6") (pinfunction "PH3_J1_6") (pintype "passive"))
    )
    (net (code "114") (name "unconnected-(M1-PH7-PadJ2_9)") (class "Default")
      (node (ref "M1") (pin "J2_9") (pinfunction "PH7_J2_9") (pintype "passive"))
    )
    (net (code "115") (name "unconnected-(M1-PH9-PadJ2_10)") (class "Default")
      (node (ref "M1") (pin "J2_10") (pinfunction "PH9_J2_10") (pintype "passive"))
    )
    (net (code "116") (name "unconnected-(M1-PH10-PadJ2_11)") (class "Default")
      (node (ref "M1") (pin "J2_11") (pinfunction "PH10_J2_11") (pintype "passive"))
    )
    (net (code "117") (name "unconnected-(M1-PH11-PadJ2_12)") (class "Default")
      (node (ref "M1") (pin "J2_12") (pinfunction "PH11_J2_12") (pintype "passive"))
    )
    (net (code "118") (name "unconnected-(M1-PH12-PadJ2_24)") (class "Default")
      (node (ref "M1") (pin "J2_24") (pinfunction "PH12_J2_24") (pintype "passive"))
    )
    (net (code "119") (name "unconnected-(M1-PH13-PadJ2_30)") (class "Default")
      (node (ref "M1") (pin "J2_30") (pinfunction "PH13_J2_30") (pintype "passive"))
    )
    (net (code "120") (name "unconnected-(M1-PH14-PadJ2_29)") (class "Default")
      (node (ref "M1") (pin "J2_29") (pinfunction "PH14_J2_29") (pintype "passive"))
    )
    (net (code "121") (name "unconnected-(M1-PH15-PadJ2_28)") (class "Default")
      (node (ref "M1") (pin "J2_28") (pinfunction "PH15_J2_28") (pintype "passive"))
    )
    (net (code "122") (name "unconnected-(M1-PI0-PadJ2_34)") (class "Default")
      (node (ref "M1") (pin "J2_34") (pinfunction "PI0_J2_34") (pintype "passive"))
    )
    (net (code "123") (name "unconnected-(M1-PI1-PadJ2_33)") (class "Default")
      (node (ref "M1") (pin "J2_33") (pinfunction "PI1_J2_33") (pintype "passive"))
    )
    (net (code "124") (name "unconnected-(M1-PI2-PadJ2_32)") (class "Default")
      (node (ref "M1") (pin "J2_32") (pinfunction "PI2_J2_32") (pintype "passive"))
    )
    (net (code "125") (name "unconnected-(M1-PI3-PadJ2_41)") (class "Default")
      (node (ref "M1") (pin "J2_41") (pinfunction "PI3_J2_41") (pintype "passive"))
    )
    (net (code "126") (name "unconnected-(M1-PI4-PadJ2_36)") (class "Default")
      (node (ref "M1") (pin "J2_36") (pinfunction "PI4_J2_36") (pintype "passive"))
    )
    (net (code "127") (name "unconnected-(M1-PI5-PadJ2_37)") (class "Default")
      (node (ref "M1") (pin "J2_37") (pinfunction "PI5_J2_37") (pintype "passive"))
    )
    (net (code "128") (name "unconnected-(M1-PI6-PadJ2_38)") (class "Default")
      (node (ref "M1") (pin "J2_38") (pinfunction "PI6_J2_38") (pintype "passive"))
    )
    (net (code "129") (name "unconnected-(M1-PI7-PadJ2_39)") (class "Default")
      (node (ref "M1") (pin "J2_39") (pinfunction "PI7_J2_39") (pintype "passive"))
    )
    (net (code "130") (name "unconnected-(M1-PI8-PadJ2_40)") (class "Default")
      (node (ref "M1") (pin "J2_40") (pinfunction "PI8_J2_40") (pintype "passive"))
    )
    (net (code "131") (name "unconnected-(M1-VBAT-PadJ1_29)") (class "Default")
      (node (ref "M1") (pin "J1_29") (pinfunction "VBAT_J1_29") (pintype "passive"))
    )
    (net (code "132") (name "unconnected-(SD_CARD-CD-Pad10)") (class "Default")
      (node (ref "SD_CARD") (pin "10") (pinfunction "CD_10") (pintype "passive"))
    )
    (net (code "133") (name "unconnected-(SD_CARD-GND-Pad11)") (class "Default")
      (node (ref "SD_CARD") (pin "11") (pinfunction "GND_11") (pintype "passive"))
    )
    (net (code "134") (name "unconnected-(SD_CARD-WP-Pad12)") (class "Default")
      (node (ref "SD_CARD") (pin "12") (pinfunction "WP_12") (pintype "passive"))
    )
    (net (code "135") (name "unconnected-(U2-AUX_CL-Pad7)") (class "Default")
      (node (ref "U2") (pin "7") (pinfunction "AUX_CL_7") (pintype "passive"))
    )
    (net (code "136") (name "unconnected-(U2-AUX_DA-Pad21)") (class "Default")
      (node (ref "U2") (pin "21") (pinfunction "AUX_DA_21") (pintype "passive"))
    )
    (net (code "137") (name "unconnected-(U2-NC-Pad2)") (class "Default")
      (node (ref "U2") (pin "2") (pinfunction "NC_2") (pintype "passive"))
    )
    (net (code "138") (name "unconnected-(U2-NC-Pad3)") (class "Default")
      (node (ref "U2") (pin "3") (pinfunction "NC_3") (pintype "passive"))
    )
    (net (code "139") (name "unconnected-(U2-NC-Pad4)") (class "Default")
      (node (ref "U2") (pin "4") (pinfunction "NC_4") (pintype "passive"))
    )
    (net (code "140") (name "unconnected-(U2-NC-Pad5)") (class "Default")
      (node (ref "U2") (pin "5") (pinfunction "NC_5") (pintype "passive"))
    )
    (net (code "141") (name "unconnected-(U2-NC-Pad6)") (class "Default")
      (node (ref "U2") (pin "6") (pinfunction "NC_6") (pintype "passive"))
    )
    (net (code "142") (name "unconnected-(U2-NC-Pad14)") (class "Default")
      (node (ref "U2") (pin "14") (pinfunction "NC_14") (pintype "passive"))
    )
    (net (code "143") (name "unconnected-(U2-NC-Pad15)") (class "Default")
      (node (ref "U2") (pin "15") (pinfunction "NC_15") (pintype "passive"))
    )
    (net (code "144") (name "unconnected-(U2-NC-Pad16)") (class "Default")
      (node (ref "U2") (pin "16") (pinfunction "NC_16") (pintype "passive"))
    )
    (net (code "145") (name "unconnected-(U2-NC-Pad17)") (class "Default")
      (node (ref "U2") (pin "17") (pinfunction "NC_17") (pintype "passive"))
    )
    (net (code "146") (name "unconnected-(U2-RESV-Pad19)") (class "Default")
      (node (ref "U2") (pin "19") (pinfunction "RESV_19") (pintype "passive"))
    )
    (net (code "147") (name "unconnected-(U2-nCS-Pad22)") (class "Default")
      (node (ref "U2") (pin "22") (pinfunction "nCS_22") (pintype "passive"))
    )
  )
)
